# Mosaic-G5.net
KiCad netlist of a schematic drawn in Altium Designer
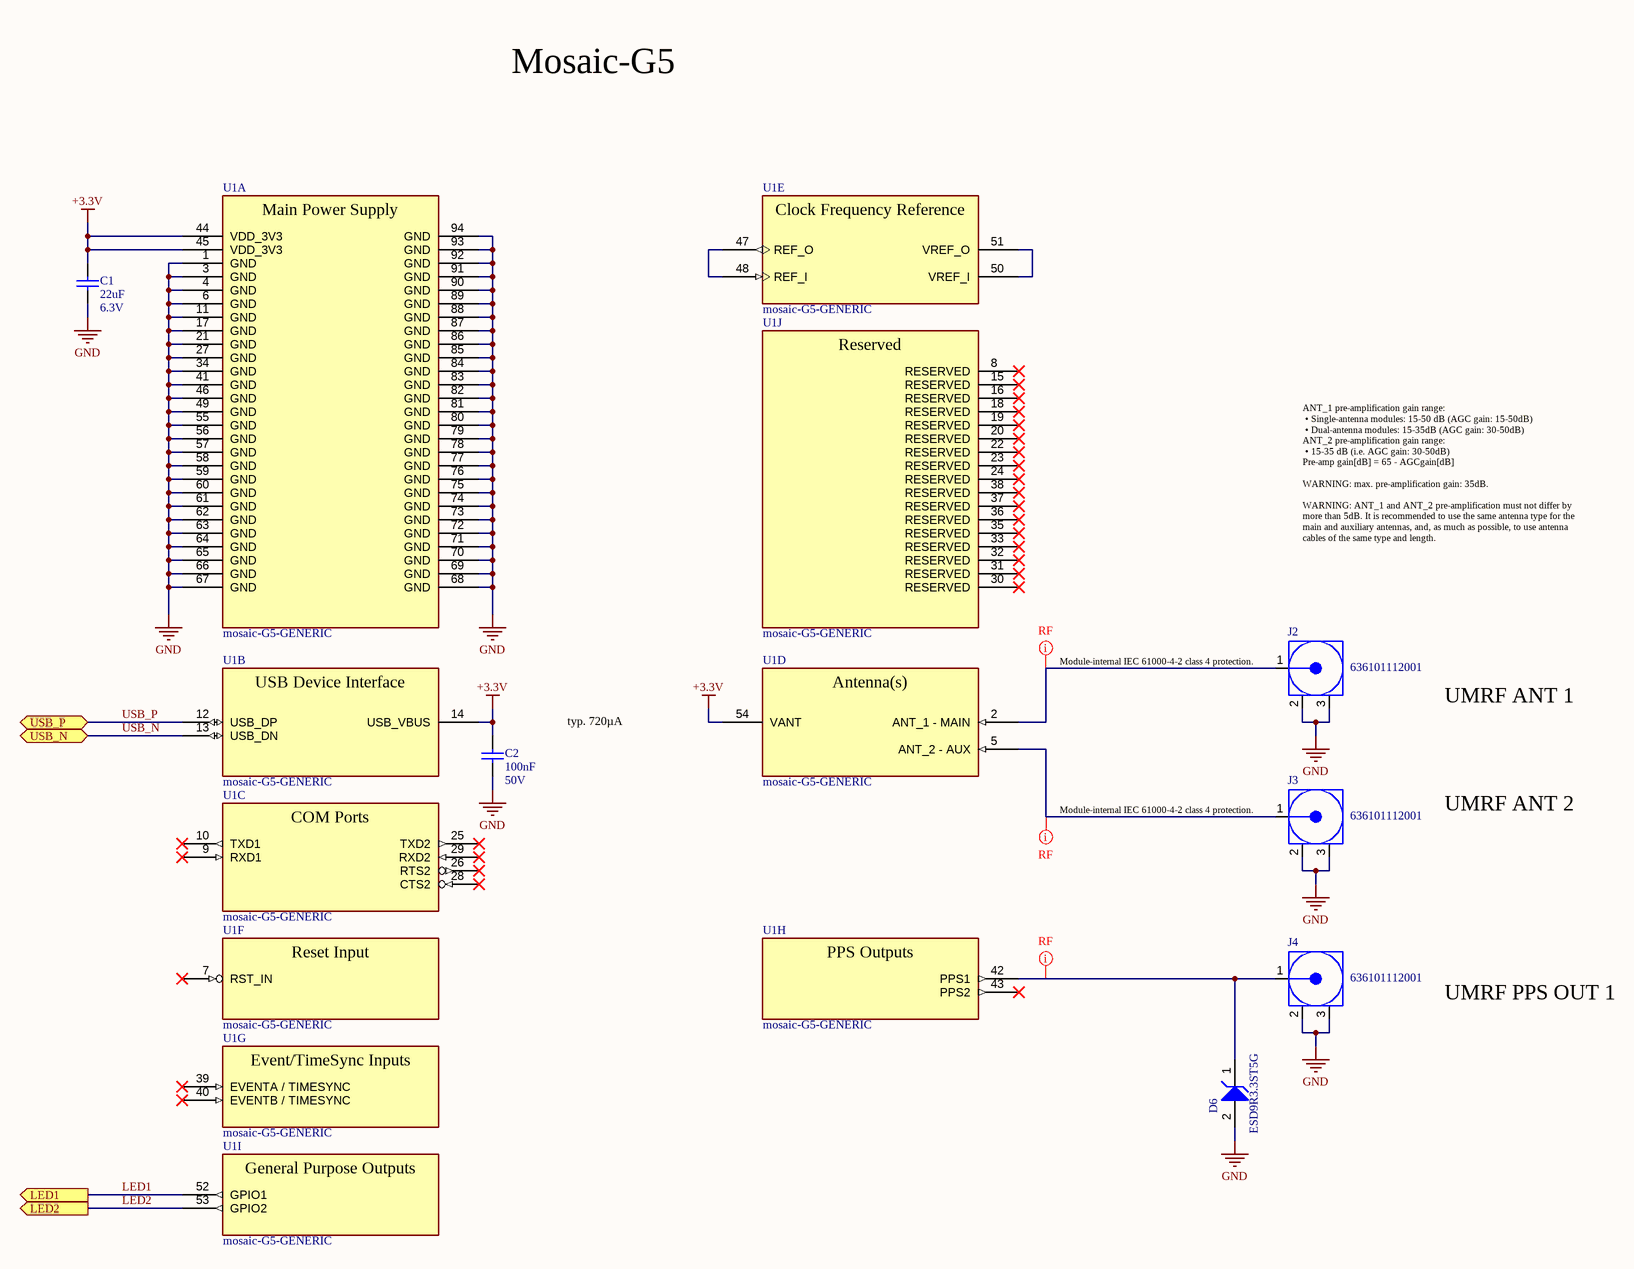
[diagram p0: Mosaic-G5.SchDoc]

(export (version "E")
  (design (tool "Eeschema 10.0.6"))
  (components
    (comp (ref "C1")
      (value "22uF")
      (footprint "CAPC1608X100X20ML10")
      (description "MLCC, 22 uF, 0603, 6.3 V, 20%, X5R")
      (fields
        (field (name "VOLTAGE") "6.3V")
        (field (name "TOLERANCE") "20%")
        (field (name "Comment") "C1608X5R0J226M080AC")
      )
      (libsource (lib "ANavS GmbH") (part "CAP"))
    )
    (comp (ref "C2")
      (value "GCM155R71H104KE02D")
      (footprint "CAP0402C")
      (description "MLCC, 100 nF, 0402, 50 V, 10%, X7R")
      (fields
        (field (name "CAPACITANCE") "100nF")
        (field (name "TOLERANCE") "10%")
        (field (name "VOLTAGE") "50V")
      )
      (libsource (lib "ANavS GmbH") (part "CAP"))
    )
    (comp (ref "D6")
      (value "ESD9R3.3ST5G")
      (footprint "ONSC-SOD-923-2-514AB-01_V")
      (description "ESD9R3.3S Series 4.8 V 0.5 pF Uni-Directional ESD Protection Diode - SOD-923")
      (libsource (lib "ANavS GmbH") (part "ONSC-K1A2-2_A"))
    )
    (comp (ref "J2")
      (value "636101112001")
      (footprint "63610111x001")
      (description "Rf Conn, Umrf, Jack, 50 Ohm, Pcb Rohs Compliant: Yes")
      (libsource (lib "ANavS GmbH") (part "Plug_2GND"))
    )
    (comp (ref "J3")
      (value "636101112001")
      (footprint "63610111x001")
      (description "Rf Conn, Umrf, Jack, 50 Ohm, Pcb Rohs Compliant: Yes")
      (libsource (lib "ANavS GmbH") (part "Plug_2GND"))
    )
    (comp (ref "J4")
      (value "636101112001")
      (footprint "63610111x001")
      (description "Rf Conn, Umrf, Jack, 50 Ohm, Pcb Rohs Compliant: Yes")
      (libsource (lib "ANavS GmbH") (part "Plug_2GND"))
    )
    (comp (ref "U1")
      (value "mosaic-G5-GENERIC")
      (footprint "mosaic-G5-GENERIC-Footprint")
      (description "mosaic-G5 GNSS Module - Low-power multi-band multi-constellation GNSS receiver.")
      (fields (field (name "MANUFACTURER") "septentrio"))
      (libsource (lib "ANavS GmbH") (part "mosaic-G5-Symbol"))
    )
  )
  (nets
    (net (code "1") (name "+3.3V") (class "Default")
      (node (ref "C1") (pin "2") (pinfunction "2_2") (pintype "passive"))
      (node (ref "C2") (pin "2") (pinfunction "2_2") (pintype "passive"))
      (node (ref "U1") (pin "14") (pinfunction "USB_VBUS_14") (pintype "power_in"))
      (node (ref "U1") (pin "44") (pinfunction "VDD_3V3_44") (pintype "power_in"))
      (node (ref "U1") (pin "45") (pinfunction "VDD_3V3_45") (pintype "power_in"))
      (node (ref "U1") (pin "54") (pinfunction "VANT_54") (pintype "power_in"))
    )
    (net (code "2") (name "/LED1") (class "Default")
      (node (ref "U1") (pin "52") (pinfunction "GPIO1_52") (pintype "output"))
    )
    (net (code "3") (name "/LED2") (class "Default")
      (node (ref "U1") (pin "53") (pinfunction "GPIO2_53") (pintype "output"))
    )
    (net (code "4") (name "/USB_N") (class "Default")
      (node (ref "U1") (pin "13") (pinfunction "USB_DN_13") (pintype "bidirectional"))
    )
    (net (code "5") (name "/USB_P") (class "Default")
      (node (ref "U1") (pin "12") (pinfunction "USB_DP_12") (pintype "bidirectional"))
    )
    (net (code "6") (name "GND") (class "Default")
      (node (ref "C1") (pin "1") (pinfunction "1_1") (pintype "passive"))
      (node (ref "C2") (pin "1") (pinfunction "1_1") (pintype "passive"))
      (node (ref "D6") (pin "2") (pinfunction "A_2") (pintype "passive"))
      (node (ref "J2") (pin "2") (pinfunction "GND_2") (pintype "passive"))
      (node (ref "J2") (pin "3") (pinfunction "GND_3") (pintype "passive"))
      (node (ref "J3") (pin "2") (pinfunction "GND_2") (pintype "passive"))
      (node (ref "J3") (pin "3") (pinfunction "GND_3") (pintype "passive"))
      (node (ref "J4") (pin "2") (pinfunction "GND_2") (pintype "passive"))
      (node (ref "J4") (pin "3") (pinfunction "GND_3") (pintype "passive"))
      (node (ref "U1") (pin "1") (pinfunction "GND_1") (pintype "power_in"))
      (node (ref "U1") (pin "11") (pinfunction "GND_11") (pintype "power_in"))
      (node (ref "U1") (pin "17") (pinfunction "GND_17") (pintype "power_in"))
      (node (ref "U1") (pin "21") (pinfunction "GND_21") (pintype "power_in"))
      (node (ref "U1") (pin "27") (pinfunction "GND_27") (pintype "power_in"))
      (node (ref "U1") (pin "3") (pinfunction "GND_3") (pintype "power_in"))
      (node (ref "U1") (pin "34") (pinfunction "GND_34") (pintype "power_in"))
      (node (ref "U1") (pin "4") (pinfunction "GND_4") (pintype "power_in"))
      (node (ref "U1") (pin "41") (pinfunction "GND_41") (pintype "power_in"))
      (node (ref "U1") (pin "46") (pinfunction "GND_46") (pintype "power_in"))
      (node (ref "U1") (pin "49") (pinfunction "GND_49") (pintype "power_in"))
      (node (ref "U1") (pin "55") (pinfunction "GND_55") (pintype "power_in"))
      (node (ref "U1") (pin "56") (pinfunction "GND_56") (pintype "power_in"))
      (node (ref "U1") (pin "57") (pinfunction "GND_57") (pintype "power_in"))
      (node (ref "U1") (pin "58") (pinfunction "GND_58") (pintype "power_in"))
      (node (ref "U1") (pin "59") (pinfunction "GND_59") (pintype "power_in"))
      (node (ref "U1") (pin "6") (pinfunction "GND_6") (pintype "power_in"))
      (node (ref "U1") (pin "60") (pinfunction "GND_60") (pintype "power_in"))
      (node (ref "U1") (pin "61") (pinfunction "GND_61") (pintype "power_in"))
      (node (ref "U1") (pin "62") (pinfunction "GND_62") (pintype "power_in"))
      (node (ref "U1") (pin "63") (pinfunction "GND_63") (pintype "power_in"))
      (node (ref "U1") (pin "64") (pinfunction "GND_64") (pintype "power_in"))
      (node (ref "U1") (pin "65") (pinfunction "GND_65") (pintype "power_in"))
      (node (ref "U1") (pin "66") (pinfunction "GND_66") (pintype "power_in"))
      (node (ref "U1") (pin "67") (pinfunction "GND_67") (pintype "power_in"))
      (node (ref "U1") (pin "68") (pinfunction "GND_68") (pintype "power_in"))
      (node (ref "U1") (pin "69") (pinfunction "GND_69") (pintype "power_in"))
      (node (ref "U1") (pin "70") (pinfunction "GND_70") (pintype "power_in"))
      (node (ref "U1") (pin "71") (pinfunction "GND_71") (pintype "power_in"))
      (node (ref "U1") (pin "72") (pinfunction "GND_72") (pintype "power_in"))
      (node (ref "U1") (pin "73") (pinfunction "GND_73") (pintype "power_in"))
      (node (ref "U1") (pin "74") (pinfunction "GND_74") (pintype "power_in"))
      (node (ref "U1") (pin "75") (pinfunction "GND_75") (pintype "power_in"))
      (node (ref "U1") (pin "76") (pinfunction "GND_76") (pintype "power_in"))
      (node (ref "U1") (pin "77") (pinfunction "GND_77") (pintype "power_in"))
      (node (ref "U1") (pin "78") (pinfunction "GND_78") (pintype "power_in"))
      (node (ref "U1") (pin "79") (pinfunction "GND_79") (pintype "power_in"))
      (node (ref "U1") (pin "80") (pinfunction "GND_80") (pintype "power_in"))
      (node (ref "U1") (pin "81") (pinfunction "GND_81") (pintype "power_in"))
      (node (ref "U1") (pin "82") (pinfunction "GND_82") (pintype "power_in"))
      (node (ref "U1") (pin "83") (pinfunction "GND_83") (pintype "power_in"))
      (node (ref "U1") (pin "84") (pinfunction "GND_84") (pintype "power_in"))
      (node (ref "U1") (pin "85") (pinfunction "GND_85") (pintype "power_in"))
      (node (ref "U1") (pin "86") (pinfunction "GND_86") (pintype "power_in"))
      (node (ref "U1") (pin "87") (pinfunction "GND_87") (pintype "power_in"))
      (node (ref "U1") (pin "88") (pinfunction "GND_88") (pintype "power_in"))
      (node (ref "U1") (pin "89") (pinfunction "GND_89") (pintype "power_in"))
      (node (ref "U1") (pin "90") (pinfunction "GND_90") (pintype "power_in"))
      (node (ref "U1") (pin "91") (pinfunction "GND_91") (pintype "power_in"))
      (node (ref "U1") (pin "92") (pinfunction "GND_92") (pintype "power_in"))
      (node (ref "U1") (pin "93") (pinfunction "GND_93") (pintype "power_in"))
      (node (ref "U1") (pin "94") (pinfunction "GND_94") (pintype "power_in"))
    )
    (net (code "7") (name "Net-(D6-K)") (class "Default")
      (node (ref "D6") (pin "1") (pinfunction "K_1") (pintype "passive"))
      (node (ref "J4") (pin "1") (pinfunction "Signal_1") (pintype "passive"))
      (node (ref "U1") (pin "42") (pinfunction "PPS1_42") (pintype "output"))
    )
    (net (code "8") (name "Net-(J2-Signal)") (class "Default")
      (node (ref "J2") (pin "1") (pinfunction "Signal_1") (pintype "passive"))
      (node (ref "U1") (pin "2") (pinfunction "ANT_1_-_MAIN_2") (pintype "input"))
    )
    (net (code "9") (name "Net-(J3-Signal)") (class "Default")
      (node (ref "J3") (pin "1") (pinfunction "Signal_1") (pintype "passive"))
      (node (ref "U1") (pin "5") (pinfunction "ANT_2_-_AUX_5") (pintype "input"))
    )
    (net (code "10") (name "Net-(U1E-REF_I)") (class "Default")
      (node (ref "U1") (pin "47") (pinfunction "REF_O_47") (pintype "output"))
      (node (ref "U1") (pin "48") (pinfunction "REF_I_48") (pintype "input"))
    )
    (net (code "11") (name "Net-(U1E-VREF_I)") (class "Default")
      (node (ref "U1") (pin "50") (pinfunction "VREF_I_50") (pintype "power_in"))
      (node (ref "U1") (pin "51") (pinfunction "VREF_O_51") (pintype "power_in"))
    )
    (net (code "12") (name "unconnected-(U1C-CTS2-Pad28)") (class "Default")
      (node (ref "U1") (pin "28") (pinfunction "CTS2_28") (pintype "input+no_connect"))
    )
    (net (code "13") (name "unconnected-(U1C-RTS2-Pad26)") (class "Default")
      (node (ref "U1") (pin "26") (pinfunction "RTS2_26") (pintype "output+no_connect"))
    )
    (net (code "14") (name "unconnected-(U1C-RXD1-Pad9)") (class "Default")
      (node (ref "U1") (pin "9") (pinfunction "RXD1_9") (pintype "input+no_connect"))
    )
    (net (code "15") (name "unconnected-(U1C-RXD2-Pad29)") (class "Default")
      (node (ref "U1") (pin "29") (pinfunction "RXD2_29") (pintype "input+no_connect"))
    )
    (net (code "16") (name "unconnected-(U1C-TXD1-Pad10)") (class "Default")
      (node (ref "U1") (pin "10") (pinfunction "TXD1_10") (pintype "output+no_connect"))
    )
    (net (code "17") (name "unconnected-(U1C-TXD2-Pad25)") (class "Default")
      (node (ref "U1") (pin "25") (pinfunction "TXD2_25") (pintype "output+no_connect"))
    )
    (net (code "18") (name "unconnected-(U1F-RST_IN-Pad7)") (class "Default")
      (node (ref "U1") (pin "7") (pinfunction "RST_IN_7") (pintype "input+no_connect"))
    )
    (net (code "19") (name "unconnected-(U1G-EVENTA_{slash}_TIMESYNC-Pad39)") (class "Default")
      (node (ref "U1") (pin "39") (pinfunction "EVENTA_/_TIMESYNC_39") (pintype "input+no_connect"))
    )
    (net (code "20") (name "unconnected-(U1G-EVENTB_{slash}_TIMESYNC-Pad40)") (class "Default")
      (node (ref "U1") (pin "40") (pinfunction "EVENTB_/_TIMESYNC_40") (pintype "input+no_connect"))
    )
    (net (code "21") (name "unconnected-(U1H-PPS2-Pad43)") (class "Default")
      (node (ref "U1") (pin "43") (pinfunction "PPS2_43") (pintype "output+no_connect"))
    )
    (net (code "22") (name "unconnected-(U1J-RESERVED-Pad8)") (class "Default")
      (node (ref "U1") (pin "8") (pinfunction "RESERVED_8") (pintype "passive+no_connect"))
    )
    (net (code "23") (name "unconnected-(U1J-RESERVED-Pad15)") (class "Default")
      (node (ref "U1") (pin "15") (pinfunction "RESERVED_15") (pintype "passive+no_connect"))
    )
    (net (code "24") (name "unconnected-(U1J-RESERVED-Pad16)") (class "Default")
      (node (ref "U1") (pin "16") (pinfunction "RESERVED_16") (pintype "passive+no_connect"))
    )
    (net (code "25") (name "unconnected-(U1J-RESERVED-Pad18)") (class "Default")
      (node (ref "U1") (pin "18") (pinfunction "RESERVED_18") (pintype "passive+no_connect"))
    )
    (net (code "26") (name "unconnected-(U1J-RESERVED-Pad19)") (class "Default")
      (node (ref "U1") (pin "19") (pinfunction "RESERVED_19") (pintype "passive+no_connect"))
    )
    (net (code "27") (name "unconnected-(U1J-RESERVED-Pad20)") (class "Default")
      (node (ref "U1") (pin "20") (pinfunction "RESERVED_20") (pintype "passive+no_connect"))
    )
    (net (code "28") (name "unconnected-(U1J-RESERVED-Pad22)") (class "Default")
      (node (ref "U1") (pin "22") (pinfunction "RESERVED_22") (pintype "passive+no_connect"))
    )
    (net (code "29") (name "unconnected-(U1J-RESERVED-Pad23)") (class "Default")
      (node (ref "U1") (pin "23") (pinfunction "RESERVED_23") (pintype "passive+no_connect"))
    )
    (net (code "30") (name "unconnected-(U1J-RESERVED-Pad24)") (class "Default")
      (node (ref "U1") (pin "24") (pinfunction "RESERVED_24") (pintype "passive+no_connect"))
    )
    (net (code "31") (name "unconnected-(U1J-RESERVED-Pad30)") (class "Default")
      (node (ref "U1") (pin "30") (pinfunction "RESERVED_30") (pintype "passive+no_connect"))
    )
    (net (code "32") (name "unconnected-(U1J-RESERVED-Pad31)") (class "Default")
      (node (ref "U1") (pin "31") (pinfunction "RESERVED_31") (pintype "passive+no_connect"))
    )
    (net (code "33") (name "unconnected-(U1J-RESERVED-Pad32)") (class "Default")
      (node (ref "U1") (pin "32") (pinfunction "RESERVED_32") (pintype "passive+no_connect"))
    )
    (net (code "34") (name "unconnected-(U1J-RESERVED-Pad33)") (class "Default")
      (node (ref "U1") (pin "33") (pinfunction "RESERVED_33") (pintype "passive+no_connect"))
    )
    (net (code "35") (name "unconnected-(U1J-RESERVED-Pad35)") (class "Default")
      (node (ref "U1") (pin "35") (pinfunction "RESERVED_35") (pintype "passive+no_connect"))
    )
    (net (code "36") (name "unconnected-(U1J-RESERVED-Pad36)") (class "Default")
      (node (ref "U1") (pin "36") (pinfunction "RESERVED_36") (pintype "passive+no_connect"))
    )
    (net (code "37") (name "unconnected-(U1J-RESERVED-Pad37)") (class "Default")
      (node (ref "U1") (pin "37") (pinfunction "RESERVED_37") (pintype "passive+no_connect"))
    )
    (net (code "38") (name "unconnected-(U1J-RESERVED-Pad38)") (class "Default")
      (node (ref "U1") (pin "38") (pinfunction "RESERVED_38") (pintype "passive+no_connect"))
    )
  )
)
